# DC_MotorDriver.net
KiCad netlist of a schematic drawn in EasyEDA Pro
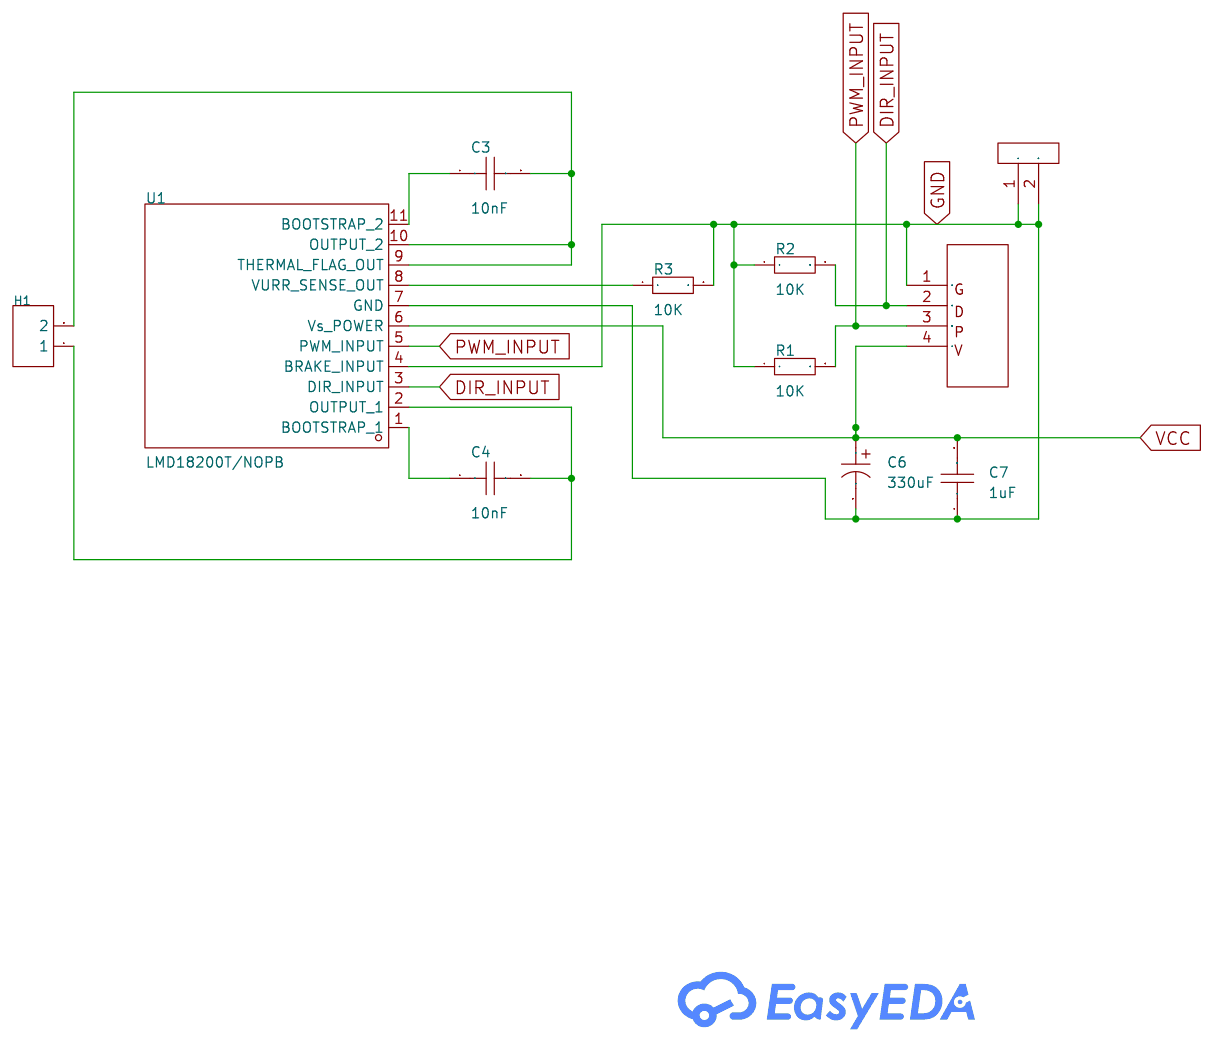
[diagram p0: schematic sheet]

(export (version "E")
  (design (tool "Eeschema 10.0.6"))
  (components
    (comp (ref "C3")
      (value "10nF")
      (footprint "easyedapro:CAP-TH_L5.8-W2.8")
      (fields
        (field (name "Manufacturer Part") "CC1H104MC1FD3F6C10SA")
        (field (name "Manufacturer") "Dersonic(德尔创)")
      )
      (libsource (lib "easyedapro") (part "CC1H104MC1FD3F6C10SA"))
    )
    (comp (ref "C4")
      (value "10nF")
      (footprint "easyedapro:CAP-TH_L5.8-W2.8")
      (fields
        (field (name "Manufacturer Part") "CC1H104MC1FD3F6C10SA")
        (field (name "Manufacturer") "Dersonic(德尔创)")
      )
      (libsource (lib "easyedapro") (part "CC1H104MC1FD3F6C10SA"))
    )
    (comp (ref "C6")
      (value "330uF")
      (footprint "easyedapro:CAP-TH_BD10.0-P5.00-D0.6-FD_2")
      (fields (field (name "Manufacturer Part") "1011001013R00") (field (name "Manufacturer") "NJCON(永立)"))
      (libsource (lib "easyedapro") (part "1011001013R00"))
    )
    (comp (ref "C7")
      (value "1uF")
      (footprint "easyedapro:CAP-TH_L5.8-W2.8")
      (fields
        (field (name "Manufacturer Part") "CC1H104MC1FD3F6C10SA")
        (field (name "Manufacturer") "Dersonic(德尔创)")
      )
      (libsource (lib "easyedapro") (part "CC1H104MC1FD3F6C10SA"))
    )
    (comp (ref "H1")
      (value "~")
      (footprint "easyedapro:HDR-TH_2P-P2.54-V-F")
      (libsource (lib "easyedapro") (part "Header-Female-2.54_1x2"))
    )
    (comp (ref "R1") (value "10K") (footprint "easyedapro:R0603") (libsource (lib "easyedapro") (part "Res")))
    (comp (ref "R2") (value "10K") (footprint "easyedapro:R0603") (libsource (lib "easyedapro") (part "Res")))
    (comp (ref "R3") (value "10K") (footprint "easyedapro:R0603") (libsource (lib "easyedapro") (part "Res")))
    (comp (ref "U1")
      (value "LMD18200T/NOPB")
      (footprint "easyedapro:TO-220-11_L20.0-W4.5-P1.70-BL")
      (fields (field (name "Manufacturer") "TI(德州仪器)"))
      (libsource (lib "easyedapro") (part "LMD18200T/NOPB"))
    )
    (comp (ref "U2")
      (value "MDriver")
      (footprint "easyedapro:DC_Main_to_Motordriver_Connector_L")
      (libsource (lib "easyedapro") (part "DC_Main_to_Motordriver_Connector"))
    )
    (comp (ref "U3")
      (value "~")
      (footprint "easyedapro:Heatsink")
      (libsource (lib "easyedapro") (part "Heatsink"))
    )
  )
  (nets
    (net (code "1") (name "DIR_INPUT") (class "Default")
      (node (ref "R2") (pin "2") (pinfunction "2_2") (pintype "input"))
      (node (ref "U1") (pin "3") (pinfunction "DIR_INPUT_3") (pintype "unspecified"))
      (node (ref "U2") (pin "2") (pinfunction "2_2") (pintype "input"))
    )
    (net (code "2") (name "GND") (class "Default")
      (node (ref "C6") (pin "2") (pinfunction "2_2") (pintype "input"))
      (node (ref "C7") (pin "1") (pinfunction "1_1") (pintype "unspecified"))
      (node (ref "R1") (pin "1") (pinfunction "1_1") (pintype "input"))
      (node (ref "R2") (pin "1") (pinfunction "1_1") (pintype "input"))
      (node (ref "R3") (pin "2") (pinfunction "2_2") (pintype "input"))
      (node (ref "U1") (pin "4") (pinfunction "BRAKE_INPUT_4") (pintype "unspecified"))
      (node (ref "U1") (pin "7") (pinfunction "GND_7") (pintype "unspecified"))
      (node (ref "U2") (pin "1") (pinfunction "1_1") (pintype "input"))
      (node (ref "U3") (pin "1") (pinfunction "1_1") (pintype "input"))
      (node (ref "U3") (pin "2") (pinfunction "2_2") (pintype "input"))
    )
    (net (code "3") (name "Net-(U1-BOOTSTRAP_1)") (class "Default")
      (node (ref "C4") (pin "1") (pinfunction "1_1") (pintype "unspecified"))
      (node (ref "U1") (pin "1") (pinfunction "BOOTSTRAP_1_1") (pintype "unspecified"))
    )
    (net (code "4") (name "Net-(U1-BOOTSTRAP_2)") (class "Default")
      (node (ref "C3") (pin "1") (pinfunction "1_1") (pintype "unspecified"))
      (node (ref "U1") (pin "11") (pinfunction "BOOTSTRAP_2_11") (pintype "unspecified"))
    )
    (net (code "5") (name "Net-(U1-OUTPUT_1)") (class "Default")
      (node (ref "C4") (pin "2") (pinfunction "2_2") (pintype "unspecified"))
      (node (ref "H1") (pin "1") (pinfunction "1_1") (pintype "input"))
      (node (ref "U1") (pin "2") (pinfunction "OUTPUT_1_2") (pintype "unspecified"))
    )
    (net (code "6") (name "Net-(U1-OUTPUT_2)") (class "Default")
      (node (ref "C3") (pin "2") (pinfunction "2_2") (pintype "unspecified"))
      (node (ref "H1") (pin "2") (pinfunction "2_2") (pintype "input"))
      (node (ref "U1") (pin "10") (pinfunction "OUTPUT_2_10") (pintype "unspecified"))
      (node (ref "U1") (pin "9") (pinfunction "THERMAL_FLAG_OUT_9") (pintype "unspecified"))
    )
    (net (code "7") (name "Net-(U1-VURR_SENSE_OUT)") (class "Default")
      (node (ref "R3") (pin "1") (pinfunction "1_1") (pintype "input"))
      (node (ref "U1") (pin "8") (pinfunction "VURR_SENSE_OUT_8") (pintype "unspecified"))
    )
    (net (code "8") (name "PWM_INPUT") (class "Default")
      (node (ref "R1") (pin "2") (pinfunction "2_2") (pintype "input"))
      (node (ref "U1") (pin "5") (pinfunction "PWM_INPUT_5") (pintype "unspecified"))
      (node (ref "U2") (pin "3") (pinfunction "3_3") (pintype "input"))
    )
    (net (code "9") (name "VCC") (class "Default")
      (node (ref "C6") (pin "1") (pinfunction "1_1") (pintype "input"))
      (node (ref "C7") (pin "2") (pinfunction "2_2") (pintype "unspecified"))
      (node (ref "U1") (pin "6") (pinfunction "Vs_POWER_6") (pintype "unspecified"))
      (node (ref "U2") (pin "4") (pinfunction "4_4") (pintype "input"))
    )
  )
)
